# dcmctrl-hb-1-board_v1.net
KiCad netlist of a schematic drawn in EAGLE
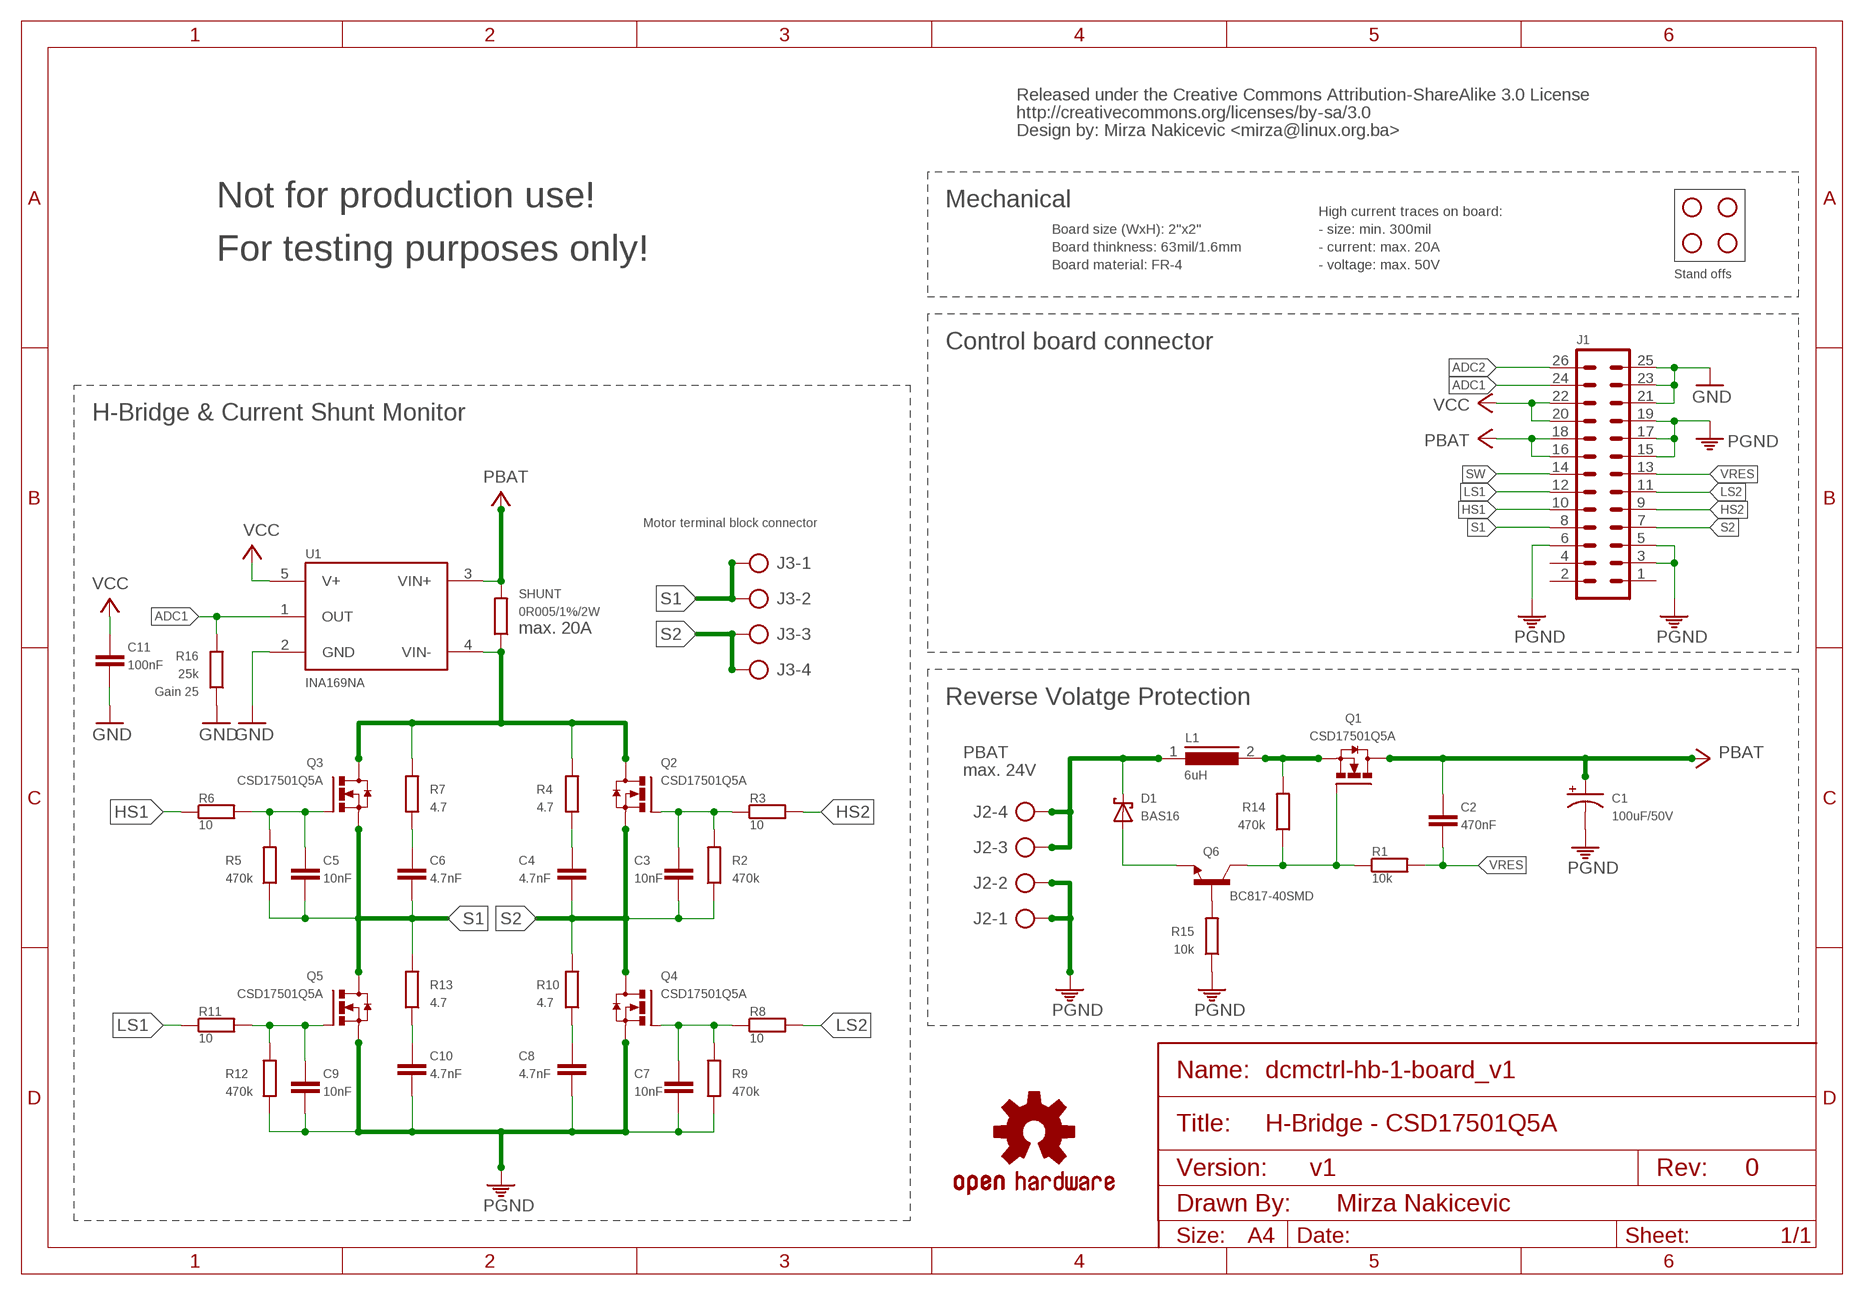
[diagram p0: schematic, sheet 1]

(export (version "E")
  (design (tool "Eeschema 10.0.6"))
  (components
    (comp (ref "C1")
      (value "100uF/50V")
      (footprint "eagle-import:E5-13")
      (libsource (lib "eagle-import") (part "CPOL-USE5-13"))
    )
    (comp (ref "C2")
      (value "470nF")
      (footprint "eagle-import:C0603")
      (libsource (lib "eagle-import") (part "C-0603"))
    )
    (comp (ref "C3")
      (value "10nF")
      (footprint "eagle-import:C0603")
      (libsource (lib "eagle-import") (part "C-0603"))
    )
    (comp (ref "C4")
      (value "4.7nF")
      (footprint "eagle-import:C0603")
      (libsource (lib "eagle-import") (part "C-0603"))
    )
    (comp (ref "C5")
      (value "10nF")
      (footprint "eagle-import:C0603")
      (libsource (lib "eagle-import") (part "C-0603"))
    )
    (comp (ref "C6")
      (value "4.7nF")
      (footprint "eagle-import:C0603")
      (libsource (lib "eagle-import") (part "C-0603"))
    )
    (comp (ref "C7")
      (value "10nF")
      (footprint "eagle-import:C0603")
      (libsource (lib "eagle-import") (part "C-0603"))
    )
    (comp (ref "C8")
      (value "4.7nF")
      (footprint "eagle-import:C0603")
      (libsource (lib "eagle-import") (part "C-0603"))
    )
    (comp (ref "C9")
      (value "10nF")
      (footprint "eagle-import:C0603")
      (libsource (lib "eagle-import") (part "C-0603"))
    )
    (comp (ref "C10")
      (value "4.7nF")
      (footprint "eagle-import:C0603")
      (libsource (lib "eagle-import") (part "C-0603"))
    )
    (comp (ref "C11")
      (value "100nF")
      (footprint "eagle-import:C0603")
      (libsource (lib "eagle-import") (part "C-0603"))
    )
    (comp (ref "D1")
      (value "BAS16")
      (footprint "eagle-import:SOT23")
      (libsource (lib "eagle-import") (part "BAS40"))
    )
    (comp (ref "J1")
      (value "MA13-2")
      (footprint "eagle-import:MA13-2")
      (libsource (lib "eagle-import") (part "MA13-2"))
    )
    (comp (ref "J2")
      (value "W237-4")
      (footprint "eagle-import:W237-4")
      (libsource (lib "eagle-import") (part "W237-4"))
    )
    (comp (ref "J3")
      (value "W237-4")
      (footprint "eagle-import:W237-4")
      (libsource (lib "eagle-import") (part "W237-4"))
    )
    (comp (ref "L1")
      (value "6uH")
      (footprint "eagle-import:DR127")
      (libsource (lib "eagle-import") (part "DR127"))
    )
    (comp (ref "Q1")
      (value "CSD17501Q5A")
      (footprint "eagle-import:Q5A")
      (libsource (lib "eagle-import") (part "CSD17501Q5A"))
    )
    (comp (ref "Q2")
      (value "CSD17501Q5A")
      (footprint "eagle-import:Q5A")
      (libsource (lib "eagle-import") (part "CSD17501Q5A"))
    )
    (comp (ref "Q3")
      (value "CSD17501Q5A")
      (footprint "eagle-import:Q5A")
      (libsource (lib "eagle-import") (part "CSD17501Q5A"))
    )
    (comp (ref "Q4")
      (value "CSD17501Q5A")
      (footprint "eagle-import:Q5A")
      (libsource (lib "eagle-import") (part "CSD17501Q5A"))
    )
    (comp (ref "Q5")
      (value "CSD17501Q5A")
      (footprint "eagle-import:Q5A")
      (libsource (lib "eagle-import") (part "CSD17501Q5A"))
    )
    (comp (ref "Q6")
      (value "BC817-40SMD")
      (footprint "eagle-import:SOT23-BEC")
      (libsource (lib "eagle-import") (part "BC817SMD-40"))
    )
    (comp (ref "R1")
      (value "10k")
      (footprint "eagle-import:R0603")
      (libsource (lib "eagle-import") (part "R-0603"))
    )
    (comp (ref "R2")
      (value "470k")
      (footprint "eagle-import:R0603")
      (libsource (lib "eagle-import") (part "R-0603"))
    )
    (comp (ref "R3")
      (value "10")
      (footprint "eagle-import:R0603")
      (libsource (lib "eagle-import") (part "R-0603"))
    )
    (comp (ref "R4")
      (value "4.7")
      (footprint "eagle-import:R0603")
      (libsource (lib "eagle-import") (part "R-0603"))
    )
    (comp (ref "R5")
      (value "470k")
      (footprint "eagle-import:R0603")
      (libsource (lib "eagle-import") (part "R-0603"))
    )
    (comp (ref "R6")
      (value "10")
      (footprint "eagle-import:R0603")
      (libsource (lib "eagle-import") (part "R-0603"))
    )
    (comp (ref "R7")
      (value "4.7")
      (footprint "eagle-import:R0603")
      (libsource (lib "eagle-import") (part "R-0603"))
    )
    (comp (ref "R8")
      (value "10")
      (footprint "eagle-import:R0603")
      (libsource (lib "eagle-import") (part "R-0603"))
    )
    (comp (ref "R9")
      (value "470k")
      (footprint "eagle-import:R0603")
      (libsource (lib "eagle-import") (part "R-0603"))
    )
    (comp (ref "R10")
      (value "4.7")
      (footprint "eagle-import:R0603")
      (libsource (lib "eagle-import") (part "R-0603"))
    )
    (comp (ref "R11")
      (value "10")
      (footprint "eagle-import:R0603")
      (libsource (lib "eagle-import") (part "R-0603"))
    )
    (comp (ref "R12")
      (value "470k")
      (footprint "eagle-import:R0603")
      (libsource (lib "eagle-import") (part "R-0603"))
    )
    (comp (ref "R13")
      (value "4.7")
      (footprint "eagle-import:R0603")
      (libsource (lib "eagle-import") (part "R-0603"))
    )
    (comp (ref "R14")
      (value "470k")
      (footprint "eagle-import:R0603")
      (libsource (lib "eagle-import") (part "R-0603"))
    )
    (comp (ref "R15")
      (value "10k")
      (footprint "eagle-import:R0603")
      (libsource (lib "eagle-import") (part "R-0603"))
    )
    (comp (ref "R16")
      (value "25k")
      (footprint "eagle-import:R0603")
      (libsource (lib "eagle-import") (part "R-0603"))
    )
    (comp (ref "SHUNT")
      (value "0R005/1%/2W")
      (footprint "eagle-import:R2512")
      (libsource (lib "eagle-import") (part "R-2512"))
    )
    (comp (ref "U$2")
      (value "STAND-OFF")
      (footprint "eagle-import:STAND-OFF")
      (libsource (lib "eagle-import") (part "STAND-OFF"))
    )
    (comp (ref "U$3")
      (value "STAND-OFF")
      (footprint "eagle-import:STAND-OFF")
      (libsource (lib "eagle-import") (part "STAND-OFF"))
    )
    (comp (ref "U$4")
      (value "STAND-OFF")
      (footprint "eagle-import:STAND-OFF")
      (libsource (lib "eagle-import") (part "STAND-OFF"))
    )
    (comp (ref "U$6")
      (value "STAND-OFF")
      (footprint "eagle-import:STAND-OFF")
      (libsource (lib "eagle-import") (part "STAND-OFF"))
    )
    (comp (ref "U$9")
      (value "CC-SA")
      (footprint "eagle-import:CC-SA")
      (libsource (lib "eagle-import") (part "CC-SA"))
    )
    (comp (ref "U$10")
      (value "OSHW-LOGOM")
      (footprint "eagle-import:OSHW-LOGO-M")
      (libsource (lib "eagle-import") (part "OSHW-LOGOM"))
    )
    (comp (ref "U1")
      (value "INA169NA")
      (footprint "eagle-import:SOT23-5")
      (libsource (lib "eagle-import") (part "INA169NA"))
    )
  )
  (nets
    (net (code "1") (name "ADC1") (class "Default")
      (node (ref "J1") (pin "24") (pinfunction "24_24") (pintype "passive"))
      (node (ref "R16") (pin "2") (pinfunction "2_2") (pintype "passive"))
      (node (ref "U1") (pin "1") (pinfunction "OUT_1") (pintype "output"))
    )
    (net (code "2") (name "ADC2") (class "Default")
      (node (ref "J1") (pin "26") (pinfunction "26_26") (pintype "passive"))
    )
    (net (code "3") (name "GND") (class "Default")
      (node (ref "C11") (pin "2") (pinfunction "2_2") (pintype "passive"))
      (node (ref "J1") (pin "21") (pinfunction "21_21") (pintype "passive"))
      (node (ref "J1") (pin "23") (pinfunction "23_23") (pintype "passive"))
      (node (ref "J1") (pin "25") (pinfunction "25_25") (pintype "passive"))
      (node (ref "R16") (pin "1") (pinfunction "1_1") (pintype "passive"))
      (node (ref "U1") (pin "2") (pinfunction "GND_2") (pintype "power_in"))
    )
    (net (code "4") (name "HS1") (class "Default")
      (node (ref "J1") (pin "10") (pinfunction "10_10") (pintype "passive"))
      (node (ref "R6") (pin "1") (pinfunction "1_1") (pintype "passive"))
    )
    (net (code "5") (name "HS2") (class "Default")
      (node (ref "J1") (pin "9") (pinfunction "9_9") (pintype "passive"))
      (node (ref "R3") (pin "2") (pinfunction "2_2") (pintype "passive"))
    )
    (net (code "6") (name "LS1") (class "Default")
      (node (ref "J1") (pin "12") (pinfunction "12_12") (pintype "passive"))
      (node (ref "R11") (pin "1") (pinfunction "1_1") (pintype "passive"))
    )
    (net (code "7") (name "LS2") (class "Default")
      (node (ref "J1") (pin "11") (pinfunction "11_11") (pintype "passive"))
      (node (ref "R8") (pin "2") (pinfunction "2_2") (pintype "passive"))
    )
    (net (code "8") (name "Net-(C4-Pad1)") (class "Default")
      (node (ref "C4") (pin "1") (pinfunction "1_1") (pintype "passive"))
      (node (ref "R4") (pin "1") (pinfunction "1_1") (pintype "passive"))
    )
    (net (code "9") (name "Net-(C6-Pad1)") (class "Default")
      (node (ref "C6") (pin "1") (pinfunction "1_1") (pintype "passive"))
      (node (ref "R7") (pin "1") (pinfunction "1_1") (pintype "passive"))
    )
    (net (code "10") (name "Net-(C8-Pad1)") (class "Default")
      (node (ref "C8") (pin "1") (pinfunction "1_1") (pintype "passive"))
      (node (ref "R10") (pin "1") (pinfunction "1_1") (pintype "passive"))
    )
    (net (code "11") (name "Net-(C10-Pad1)") (class "Default")
      (node (ref "C10") (pin "1") (pinfunction "1_1") (pintype "passive"))
      (node (ref "R13") (pin "1") (pinfunction "1_1") (pintype "passive"))
    )
    (net (code "12") (name "Net-(D1-A)") (class "Default")
      (node (ref "D1") (pin "1") (pinfunction "A_1") (pintype "passive"))
      (node (ref "Q6") (pin "E") (pinfunction "E_E") (pintype "passive"))
    )
    (net (code "13") (name "Net-(D1-C)") (class "Default")
      (node (ref "D1") (pin "3") (pinfunction "C_3") (pintype "passive"))
      (node (ref "J2") (pin "3") (pinfunction "KL_3") (pintype "passive"))
      (node (ref "J2") (pin "4") (pinfunction "KL_4") (pintype "passive"))
      (node (ref "L1") (pin "1") (pinfunction "1_1") (pintype "passive"))
    )
    (net (code "14") (name "Net-(L1-Pad2)") (class "Default")
      (node (ref "L1") (pin "2") (pinfunction "2_2") (pintype "passive"))
      (node (ref "Q1") (pin "1") (pinfunction "S_1") (pintype "passive"))
      (node (ref "Q1") (pin "2") (pinfunction "S_2") (pintype "passive"))
      (node (ref "Q1") (pin "3") (pinfunction "S_3") (pintype "passive"))
      (node (ref "R14") (pin "2") (pinfunction "2_2") (pintype "passive"))
    )
    (net (code "15") (name "Net-(Q1-G)") (class "Default")
      (node (ref "Q1") (pin "4") (pinfunction "G_4") (pintype "passive"))
      (node (ref "Q6") (pin "C") (pinfunction "C_C") (pintype "passive"))
      (node (ref "R1") (pin "1") (pinfunction "1_1") (pintype "passive"))
      (node (ref "R14") (pin "1") (pinfunction "1_1") (pintype "passive"))
    )
    (net (code "16") (name "Net-(Q2-G)") (class "Default")
      (node (ref "C3") (pin "1") (pinfunction "1_1") (pintype "passive"))
      (node (ref "Q2") (pin "4") (pinfunction "G_4") (pintype "passive"))
      (node (ref "R2") (pin "2") (pinfunction "2_2") (pintype "passive"))
      (node (ref "R3") (pin "1") (pinfunction "1_1") (pintype "passive"))
    )
    (net (code "17") (name "Net-(Q3-G)") (class "Default")
      (node (ref "C5") (pin "1") (pinfunction "1_1") (pintype "passive"))
      (node (ref "Q3") (pin "4") (pinfunction "G_4") (pintype "passive"))
      (node (ref "R5") (pin "2") (pinfunction "2_2") (pintype "passive"))
      (node (ref "R6") (pin "2") (pinfunction "2_2") (pintype "passive"))
    )
    (net (code "18") (name "Net-(Q4-G)") (class "Default")
      (node (ref "C7") (pin "1") (pinfunction "1_1") (pintype "passive"))
      (node (ref "Q4") (pin "4") (pinfunction "G_4") (pintype "passive"))
      (node (ref "R8") (pin "1") (pinfunction "1_1") (pintype "passive"))
      (node (ref "R9") (pin "2") (pinfunction "2_2") (pintype "passive"))
    )
    (net (code "19") (name "Net-(Q5-G)") (class "Default")
      (node (ref "C9") (pin "1") (pinfunction "1_1") (pintype "passive"))
      (node (ref "Q5") (pin "4") (pinfunction "G_4") (pintype "passive"))
      (node (ref "R11") (pin "2") (pinfunction "2_2") (pintype "passive"))
      (node (ref "R12") (pin "2") (pinfunction "2_2") (pintype "passive"))
    )
    (net (code "20") (name "Net-(Q6-PadB)") (class "Default")
      (node (ref "Q6") (pin "B") (pinfunction "B_B") (pintype "passive"))
      (node (ref "R15") (pin "2") (pinfunction "2_2") (pintype "passive"))
    )
    (net (code "21") (name "Net-(U1-VIN-)") (class "Default")
      (node (ref "Q2") (pin "5") (pinfunction "D_5") (pintype "passive"))
      (node (ref "Q2") (pin "6") (pinfunction "D_6") (pintype "passive"))
      (node (ref "Q2") (pin "7") (pinfunction "D_7") (pintype "passive"))
      (node (ref "Q2") (pin "8") (pinfunction "D_8") (pintype "passive"))
      (node (ref "Q2") (pin "TP") (pinfunction "D_TP") (pintype "passive"))
      (node (ref "Q3") (pin "5") (pinfunction "D_5") (pintype "passive"))
      (node (ref "Q3") (pin "6") (pinfunction "D_6") (pintype "passive"))
      (node (ref "Q3") (pin "7") (pinfunction "D_7") (pintype "passive"))
      (node (ref "Q3") (pin "8") (pinfunction "D_8") (pintype "passive"))
      (node (ref "Q3") (pin "TP") (pinfunction "D_TP") (pintype "passive"))
      (node (ref "R4") (pin "2") (pinfunction "2_2") (pintype "passive"))
      (node (ref "R7") (pin "2") (pinfunction "2_2") (pintype "passive"))
      (node (ref "SHUNT") (pin "1") (pinfunction "1_1") (pintype "passive"))
      (node (ref "U1") (pin "4") (pinfunction "VIN-_4") (pintype "passive"))
    )
    (net (code "22") (name "PBAT") (class "Default")
      (node (ref "C1") (pin "+") (pinfunction "+_+") (pintype "passive"))
      (node (ref "C2") (pin "1") (pinfunction "1_1") (pintype "passive"))
      (node (ref "J1") (pin "16") (pinfunction "16_16") (pintype "passive"))
      (node (ref "J1") (pin "18") (pinfunction "18_18") (pintype "passive"))
      (node (ref "Q1") (pin "5") (pinfunction "D_5") (pintype "passive"))
      (node (ref "Q1") (pin "6") (pinfunction "D_6") (pintype "passive"))
      (node (ref "Q1") (pin "7") (pinfunction "D_7") (pintype "passive"))
      (node (ref "Q1") (pin "8") (pinfunction "D_8") (pintype "passive"))
      (node (ref "Q1") (pin "TP") (pinfunction "D_TP") (pintype "passive"))
      (node (ref "SHUNT") (pin "2") (pinfunction "2_2") (pintype "passive"))
      (node (ref "U1") (pin "3") (pinfunction "VIN+_3") (pintype "passive"))
    )
    (net (code "23") (name "PGND") (class "Default")
      (node (ref "C1") (pin "-") (pinfunction "-_-") (pintype "passive"))
      (node (ref "C10") (pin "2") (pinfunction "2_2") (pintype "passive"))
      (node (ref "C7") (pin "2") (pinfunction "2_2") (pintype "passive"))
      (node (ref "C8") (pin "2") (pinfunction "2_2") (pintype "passive"))
      (node (ref "C9") (pin "2") (pinfunction "2_2") (pintype "passive"))
      (node (ref "J1") (pin "15") (pinfunction "15_15") (pintype "passive"))
      (node (ref "J1") (pin "17") (pinfunction "17_17") (pintype "passive"))
      (node (ref "J1") (pin "19") (pinfunction "19_19") (pintype "passive"))
      (node (ref "J1") (pin "3") (pinfunction "3_3") (pintype "passive"))
      (node (ref "J1") (pin "5") (pinfunction "5_5") (pintype "passive"))
      (node (ref "J1") (pin "6") (pinfunction "6_6") (pintype "passive"))
      (node (ref "J2") (pin "1") (pinfunction "KL_1") (pintype "passive"))
      (node (ref "J2") (pin "2") (pinfunction "KL_2") (pintype "passive"))
      (node (ref "Q4") (pin "1") (pinfunction "S_1") (pintype "passive"))
      (node (ref "Q4") (pin "2") (pinfunction "S_2") (pintype "passive"))
      (node (ref "Q4") (pin "3") (pinfunction "S_3") (pintype "passive"))
      (node (ref "Q5") (pin "1") (pinfunction "S_1") (pintype "passive"))
      (node (ref "Q5") (pin "2") (pinfunction "S_2") (pintype "passive"))
      (node (ref "Q5") (pin "3") (pinfunction "S_3") (pintype "passive"))
      (node (ref "R12") (pin "1") (pinfunction "1_1") (pintype "passive"))
      (node (ref "R15") (pin "1") (pinfunction "1_1") (pintype "passive"))
      (node (ref "R9") (pin "1") (pinfunction "1_1") (pintype "passive"))
    )
    (net (code "24") (name "S1") (class "Default")
      (node (ref "C5") (pin "2") (pinfunction "2_2") (pintype "passive"))
      (node (ref "C6") (pin "2") (pinfunction "2_2") (pintype "passive"))
      (node (ref "J1") (pin "8") (pinfunction "8_8") (pintype "passive"))
      (node (ref "J3") (pin "1") (pinfunction "KL_1") (pintype "passive"))
      (node (ref "J3") (pin "2") (pinfunction "KL_2") (pintype "passive"))
      (node (ref "Q3") (pin "1") (pinfunction "S_1") (pintype "passive"))
      (node (ref "Q3") (pin "2") (pinfunction "S_2") (pintype "passive"))
      (node (ref "Q3") (pin "3") (pinfunction "S_3") (pintype "passive"))
      (node (ref "Q5") (pin "5") (pinfunction "D_5") (pintype "passive"))
      (node (ref "Q5") (pin "6") (pinfunction "D_6") (pintype "passive"))
      (node (ref "Q5") (pin "7") (pinfunction "D_7") (pintype "passive"))
      (node (ref "Q5") (pin "8") (pinfunction "D_8") (pintype "passive"))
      (node (ref "Q5") (pin "TP") (pinfunction "D_TP") (pintype "passive"))
      (node (ref "R13") (pin "2") (pinfunction "2_2") (pintype "passive"))
      (node (ref "R5") (pin "1") (pinfunction "1_1") (pintype "passive"))
    )
    (net (code "25") (name "S2") (class "Default")
      (node (ref "C3") (pin "2") (pinfunction "2_2") (pintype "passive"))
      (node (ref "C4") (pin "2") (pinfunction "2_2") (pintype "passive"))
      (node (ref "J1") (pin "7") (pinfunction "7_7") (pintype "passive"))
      (node (ref "J3") (pin "3") (pinfunction "KL_3") (pintype "passive"))
      (node (ref "J3") (pin "4") (pinfunction "KL_4") (pintype "passive"))
      (node (ref "Q2") (pin "1") (pinfunction "S_1") (pintype "passive"))
      (node (ref "Q2") (pin "2") (pinfunction "S_2") (pintype "passive"))
      (node (ref "Q2") (pin "3") (pinfunction "S_3") (pintype "passive"))
      (node (ref "Q4") (pin "5") (pinfunction "D_5") (pintype "passive"))
      (node (ref "Q4") (pin "6") (pinfunction "D_6") (pintype "passive"))
      (node (ref "Q4") (pin "7") (pinfunction "D_7") (pintype "passive"))
      (node (ref "Q4") (pin "8") (pinfunction "D_8") (pintype "passive"))
      (node (ref "Q4") (pin "TP") (pinfunction "D_TP") (pintype "passive"))
      (node (ref "R10") (pin "2") (pinfunction "2_2") (pintype "passive"))
      (node (ref "R2") (pin "1") (pinfunction "1_1") (pintype "passive"))
    )
    (net (code "26") (name "SW") (class "Default")
      (node (ref "J1") (pin "14") (pinfunction "14_14") (pintype "passive"))
    )
    (net (code "27") (name "VCC") (class "Default")
      (node (ref "C11") (pin "1") (pinfunction "1_1") (pintype "passive"))
      (node (ref "J1") (pin "20") (pinfunction "20_20") (pintype "passive"))
      (node (ref "J1") (pin "22") (pinfunction "22_22") (pintype "passive"))
      (node (ref "U1") (pin "5") (pinfunction "V+_5") (pintype "power_in"))
    )
    (net (code "28") (name "VRES") (class "Default")
      (node (ref "C2") (pin "2") (pinfunction "2_2") (pintype "passive"))
      (node (ref "J1") (pin "13") (pinfunction "13_13") (pintype "passive"))
      (node (ref "R1") (pin "2") (pinfunction "2_2") (pintype "passive"))
    )
    (net (code "29") (name "unconnected-(J1-Pad1)") (class "Default")
      (node (ref "J1") (pin "1") (pinfunction "1_1") (pintype "passive"))
    )
    (net (code "30") (name "unconnected-(J1-Pad2)") (class "Default")
      (node (ref "J1") (pin "2") (pinfunction "2_2") (pintype "passive"))
    )
    (net (code "31") (name "unconnected-(J1-Pad4)") (class "Default")
      (node (ref "J1") (pin "4") (pinfunction "4_4") (pintype "passive"))
    )
  )
)
